# 5V_Supply_and_Protection.net
KiCad netlist of a schematic drawn in Altium Designer
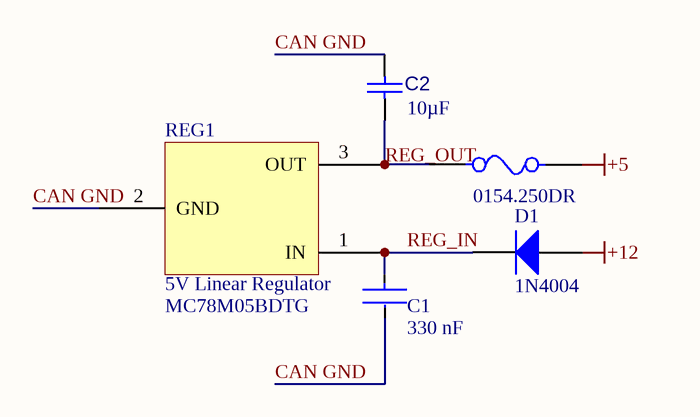
[diagram p0: 5V Supply and Protection.SchDoc]

(export (version "E")
  (design (tool "Eeschema 10.0.6"))
  (components
    (comp (ref "C1")
      (value "330 nF")
      (footprint "FP-CC0603-DA-MFG")
      (description "CAP CER 0.33UF 16V X7R 0603")
      (fields
        (field (name "OCTOPART") "https://octopart.com/cc0603krx7r7bb334-yageo-9291796")
        (field (name "MANUFACTURER") "YAGEO")
      )
      (libsource (lib "Altium Content Vault") (part "11868f565c42a9108669ba33697ecf6"))
    )
    (comp (ref "C2")
      (value "10µF")
      (footprint "CAPC0603(1608)100_L")
      (description "Chip Capacitor, 10µF +/-20%, 10V, 0603, Thickness 1 mm")
      (fields (field (name "TOLERANCE") "10%") (field (name "Comment") "Capacitor 10µF +/-20% 10V 0603"))
      (libsource (lib "WashU Racing") (part "CAP-NP-2"))
    )
    (comp (ref "D1")
      (value "1N4004")
      (footprint "FAIR-DO-41-2")
      (fields (field (name "MANUFACTURER") "Fairchild Semiconductor"))
      (libsource (lib "WashU Racing") (part "D-AK-2"))
    )
    (comp (ref "FUSE")
      (value "0154.250DR")
      (footprint "FP-0154-MFG")
      (description "FUSE BOARD MNT 250MA 125VAC/VDC")
      (fields
        (field (name "MANUFACTURER") "Littelfuse")
        (field (name "OCTOPART") "https://octopart.com/0154.250dr-littelfuse-565851")
      )
      (libsource (lib "Altium Content Vault") (part "5bcf9b9f640e542cf0359d10258e979"))
    )
    (comp (ref "REG1")
      (value "MC78M05BDTG")
      (footprint "DPAK3")
      (description "IC REG LINEAR 5V 0.5A DPAK3")
      (libsource (lib "MC78M05BDTG") (part "MC78M05BDTG"))
    )
  )
  (nets
    (net (code "1") (name "+5") (class "Default")
      (node (ref "FUSE") (pin "2") (pinfunction "2_2") (pintype "passive"))
    )
    (net (code "2") (name "+12") (class "Default")
      (node (ref "D1") (pin "1") (pinfunction "A_1") (pintype "passive"))
    )
    (net (code "3") (name "/CAN GND") (class "Default")
      (node (ref "C1") (pin "2") (pinfunction "2_2") (pintype "passive"))
      (node (ref "C2") (pin "2") (pinfunction "2_2") (pintype "passive"))
      (node (ref "REG1") (pin "2") (pinfunction "GND_2") (pintype "passive"))
    )
    (net (code "4") (name "/REG_IN") (class "Default")
      (node (ref "C1") (pin "1") (pinfunction "1_1") (pintype "passive"))
      (node (ref "D1") (pin "2") (pinfunction "K_2") (pintype "passive"))
      (node (ref "REG1") (pin "1") (pinfunction "IN_1") (pintype "passive"))
    )
    (net (code "5") (name "/REG_OUT") (class "Default")
      (node (ref "C2") (pin "1") (pinfunction "1_1") (pintype "passive"))
      (node (ref "FUSE") (pin "1") (pinfunction "1_1") (pintype "passive"))
      (node (ref "REG1") (pin "3") (pinfunction "OUT_3") (pintype "passive"))
    )
  )
)
